# SHASwitch3.net
KiCad netlist of a schematic drawn in EAGLE
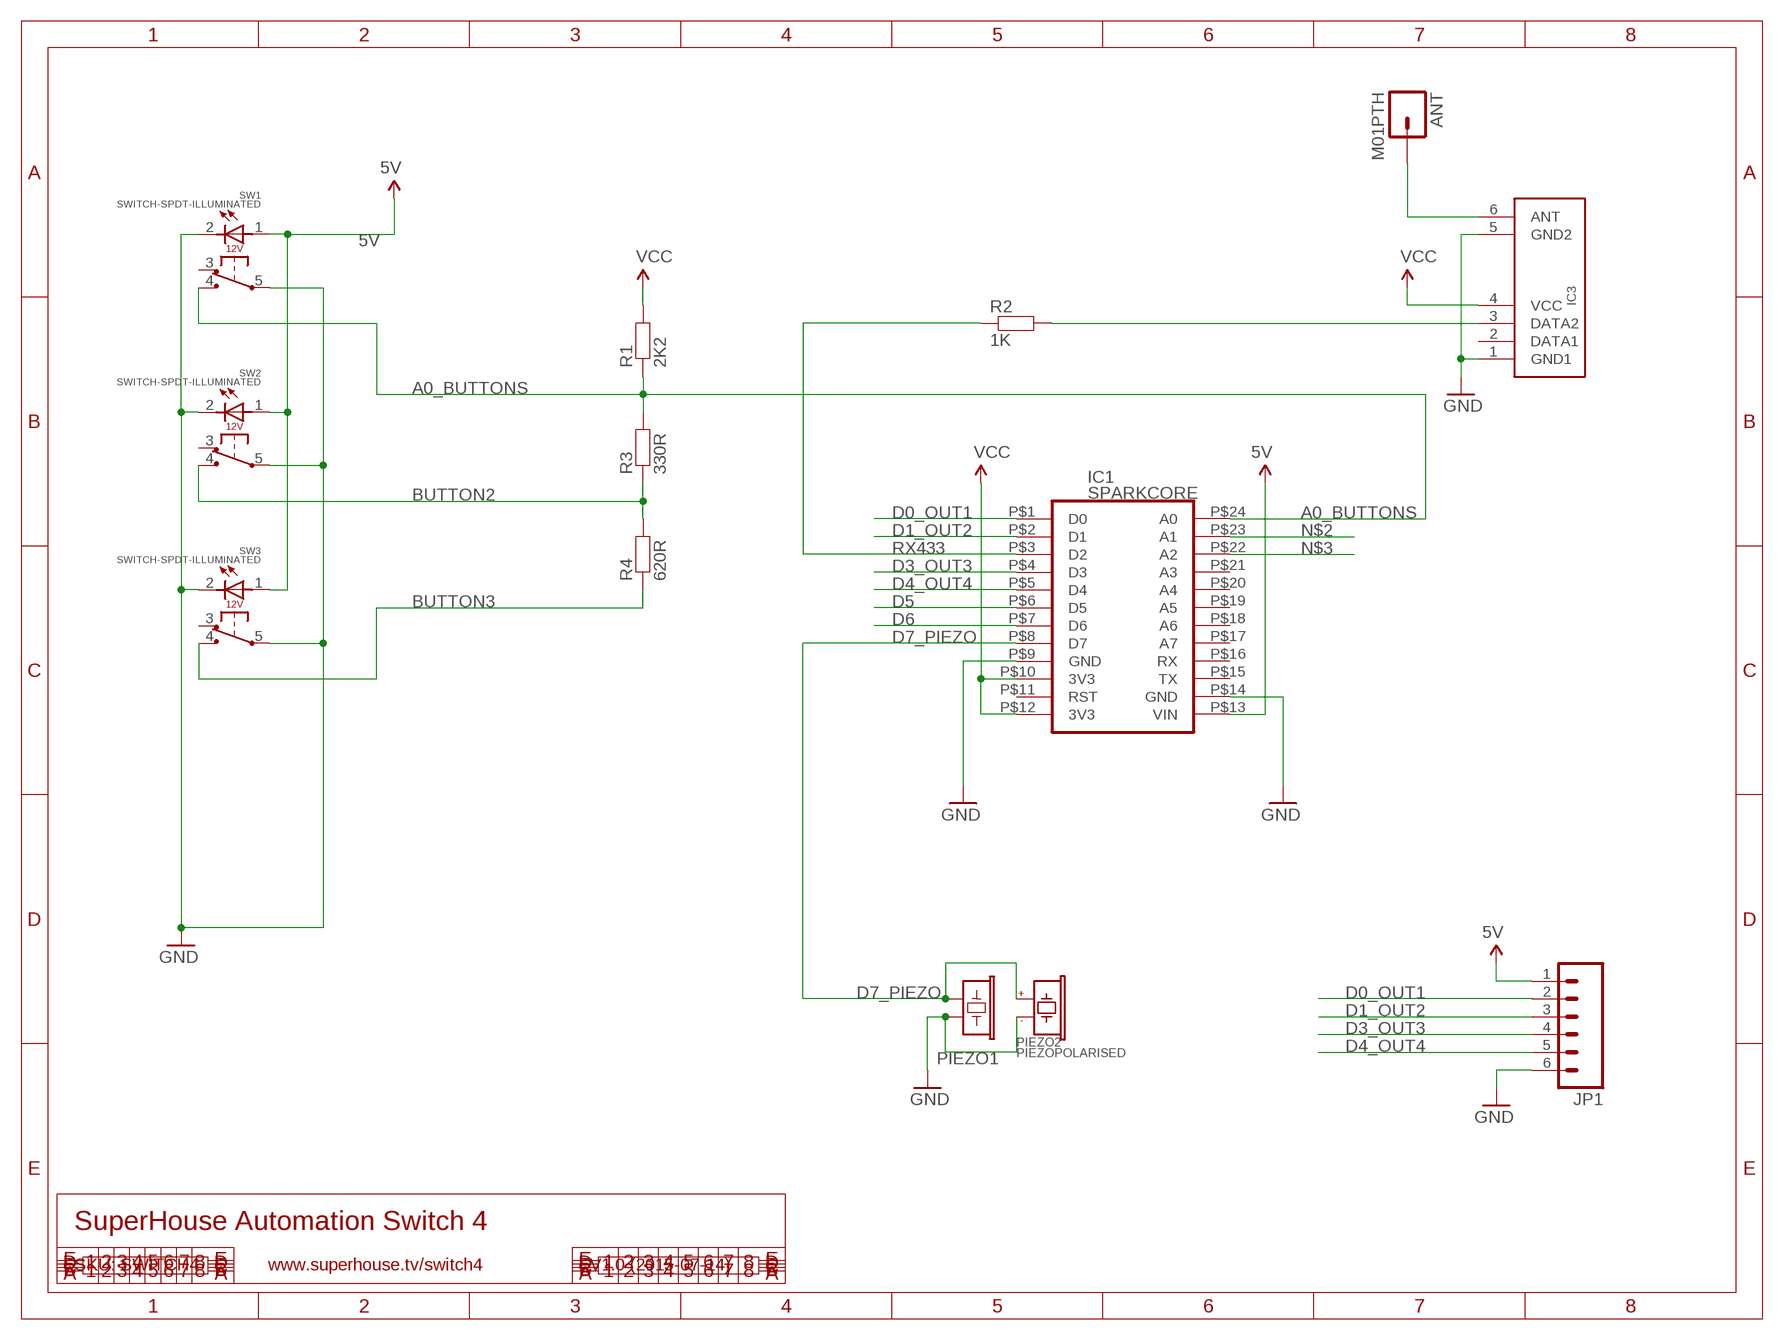
[diagram p0: schematic, sheet 1]

(export (version "E")
  (design (tool "Eeschema 10.0.6"))
  (components
    (comp (ref "ANT")
      (value "M01PTH")
      (footprint "eagle-import:1X01")
      (libsource (lib "eagle-import") (part "M01PTH"))
    )
    (comp (ref "IC1")
      (value "SPARKCORE")
      (footprint "eagle-import:SPARKCORE")
      (libsource (lib "eagle-import") (part "SPARKCORE"))
    )
    (comp (ref "IC3")
      (value "RXB1")
      (footprint "eagle-import:RX-B1-SHORT-FLAT")
      (libsource (lib "eagle-import") (part "RXB1SHORTFLAT"))
    )
    (comp (ref "JP1")
      (value "M06SIP")
      (footprint "eagle-import:1X06")
      (libsource (lib "eagle-import") (part "M06SIP"))
    )
    (comp (ref "PIEZO1")
      (value "BUZZERSMD12X12")
      (footprint "eagle-import:BUZZER-12X12-SMT")
      (libsource (lib "eagle-import") (part "BUZZERSMD12X12"))
    )
    (comp (ref "PIEZO2")
      (value "PIEZOPOLARISED")
      (footprint "eagle-import:PIEZO12MMWIDEPOLARISED")
      (libsource (lib "eagle-import") (part "PIEZOPOLARISED"))
    )
    (comp (ref "R1")
      (value "2K2")
      (footprint "eagle-import:0603")
      (libsource (lib "eagle-import") (part "RESISTOR0603"))
    )
    (comp (ref "R2")
      (value "1K")
      (footprint "eagle-import:0603")
      (libsource (lib "eagle-import") (part "RESISTOR0603"))
    )
    (comp (ref "R3")
      (value "330R")
      (footprint "eagle-import:0603")
      (libsource (lib "eagle-import") (part "RESISTOR0603"))
    )
    (comp (ref "R4")
      (value "620R")
      (footprint "eagle-import:0603")
      (libsource (lib "eagle-import") (part "RESISTOR0603"))
    )
    (comp (ref "SW1")
      (value "SWITCH-SPDT-ILLUMINATED")
      (footprint "eagle-import:SWITCH-SPDT-ILLUMINATED")
      (libsource (lib "eagle-import") (part "SWITCH-SPDT-ILLUMINATED"))
    )
    (comp (ref "SW2")
      (value "SWITCH-SPDT-ILLUMINATED")
      (footprint "eagle-import:SWITCH-SPDT-ILLUMINATED")
      (libsource (lib "eagle-import") (part "SWITCH-SPDT-ILLUMINATED"))
    )
    (comp (ref "SW3")
      (value "SWITCH-SPDT-ILLUMINATED")
      (footprint "eagle-import:SWITCH-SPDT-ILLUMINATED")
      (libsource (lib "eagle-import") (part "SWITCH-SPDT-ILLUMINATED"))
    )
  )
  (nets
    (net (code "1") (name "/A0_BUTTONS") (class "Default")
      (node (ref "IC1") (pin "P$24") (pinfunction "A0_P$24") (pintype "bidirectional"))
      (node (ref "R1") (pin "1") (pinfunction "1_1") (pintype "passive"))
      (node (ref "R3") (pin "2") (pinfunction "2_2") (pintype "passive"))
      (node (ref "SW1") (pin "4") (pinfunction "NO_4") (pintype "passive"))
    )
    (net (code "2") (name "/BUTTON2") (class "Default")
      (node (ref "R3") (pin "1") (pinfunction "1_1") (pintype "passive"))
      (node (ref "R4") (pin "2") (pinfunction "2_2") (pintype "passive"))
      (node (ref "SW2") (pin "4") (pinfunction "NO_4") (pintype "passive"))
    )
    (net (code "3") (name "/BUTTON3") (class "Default")
      (node (ref "R4") (pin "1") (pinfunction "1_1") (pintype "passive"))
      (node (ref "SW3") (pin "4") (pinfunction "NO_4") (pintype "passive"))
    )
    (net (code "4") (name "/D0_OUT1") (class "Default")
      (node (ref "IC1") (pin "P$1") (pinfunction "D0_P$1") (pintype "bidirectional"))
      (node (ref "JP1") (pin "2") (pinfunction "2_2") (pintype "passive"))
    )
    (net (code "5") (name "/D1_OUT2") (class "Default")
      (node (ref "IC1") (pin "P$2") (pinfunction "D1_P$2") (pintype "bidirectional"))
      (node (ref "JP1") (pin "3") (pinfunction "3_3") (pintype "passive"))
    )
    (net (code "6") (name "/D3_OUT3") (class "Default")
      (node (ref "IC1") (pin "P$4") (pinfunction "D3_P$4") (pintype "bidirectional"))
      (node (ref "JP1") (pin "4") (pinfunction "4_4") (pintype "passive"))
    )
    (net (code "7") (name "/D4_OUT4") (class "Default")
      (node (ref "IC1") (pin "P$5") (pinfunction "D4_P$5") (pintype "bidirectional"))
      (node (ref "JP1") (pin "5") (pinfunction "5_5") (pintype "passive"))
    )
    (net (code "8") (name "/D5") (class "Default")
      (node (ref "IC1") (pin "P$6") (pinfunction "D5_P$6") (pintype "bidirectional"))
    )
    (net (code "9") (name "/D6") (class "Default")
      (node (ref "IC1") (pin "P$7") (pinfunction "D6_P$7") (pintype "bidirectional"))
    )
    (net (code "10") (name "/D7_PIEZO") (class "Default")
      (node (ref "IC1") (pin "P$8") (pinfunction "D7_P$8") (pintype "bidirectional"))
      (node (ref "PIEZO1") (pin "1") (pinfunction "1_1") (pintype "passive"))
      (node (ref "PIEZO2") (pin "1") (pinfunction "+_1") (pintype "bidirectional"))
    )
    (net (code "11") (name "/N$2") (class "Default")
      (node (ref "IC1") (pin "P$23") (pinfunction "A1_P$23") (pintype "bidirectional"))
    )
    (net (code "12") (name "/N$3") (class "Default")
      (node (ref "IC1") (pin "P$22") (pinfunction "A2_P$22") (pintype "bidirectional"))
    )
    (net (code "13") (name "/RX433") (class "Default")
      (node (ref "IC1") (pin "P$3") (pinfunction "D2_P$3") (pintype "bidirectional"))
      (node (ref "R2") (pin "1") (pinfunction "1_1") (pintype "passive"))
    )
    (net (code "14") (name "5V") (class "Default")
      (node (ref "IC1") (pin "P$13") (pinfunction "VIN_P$13") (pintype "bidirectional"))
      (node (ref "JP1") (pin "1") (pinfunction "1_1") (pintype "passive"))
      (node (ref "SW1") (pin "1") (pinfunction "+_1") (pintype "passive"))
      (node (ref "SW2") (pin "1") (pinfunction "+_1") (pintype "passive"))
      (node (ref "SW3") (pin "1") (pinfunction "+_1") (pintype "passive"))
    )
    (net (code "15") (name "GND") (class "Default")
      (node (ref "IC1") (pin "P$14") (pinfunction "GND_P$14") (pintype "bidirectional"))
      (node (ref "IC1") (pin "P$9") (pinfunction "GND_P$9") (pintype "bidirectional"))
      (node (ref "IC3") (pin "1") (pinfunction "GND1_1") (pintype "bidirectional"))
      (node (ref "IC3") (pin "5") (pinfunction "GND2_5") (pintype "bidirectional"))
      (node (ref "JP1") (pin "6") (pinfunction "6_6") (pintype "passive"))
      (node (ref "PIEZO1") (pin "2") (pinfunction "2_2") (pintype "passive"))
      (node (ref "PIEZO2") (pin "2") (pinfunction "-_2") (pintype "bidirectional"))
      (node (ref "SW1") (pin "2") (pinfunction "-_2") (pintype "passive"))
      (node (ref "SW1") (pin "5") (pinfunction "COM_5") (pintype "passive"))
      (node (ref "SW2") (pin "2") (pinfunction "-_2") (pintype "passive"))
      (node (ref "SW2") (pin "5") (pinfunction "COM_5") (pintype "passive"))
      (node (ref "SW3") (pin "2") (pinfunction "-_2") (pintype "passive"))
      (node (ref "SW3") (pin "5") (pinfunction "COM_5") (pintype "passive"))
    )
    (net (code "16") (name "Net-(IC3-ANT)") (class "Default")
      (node (ref "ANT") (pin "1") (pinfunction "1_1") (pintype "passive"))
      (node (ref "IC3") (pin "6") (pinfunction "ANT_6") (pintype "bidirectional"))
    )
    (net (code "17") (name "Net-(IC3-DATA2)") (class "Default")
      (node (ref "IC3") (pin "3") (pinfunction "DATA2_3") (pintype "bidirectional"))
      (node (ref "R2") (pin "2") (pinfunction "2_2") (pintype "passive"))
    )
    (net (code "18") (name "VCC") (class "Default")
      (node (ref "IC1") (pin "P$10") (pinfunction "3V3_P$10") (pintype "bidirectional"))
      (node (ref "IC1") (pin "P$12") (pinfunction "3V3_P$12") (pintype "bidirectional"))
      (node (ref "IC3") (pin "4") (pinfunction "VCC_4") (pintype "bidirectional"))
      (node (ref "R1") (pin "2") (pinfunction "2_2") (pintype "passive"))
    )
    (net (code "19") (name "unconnected-(IC1-A3-PadP$21)") (class "Default")
      (node (ref "IC1") (pin "P$21") (pinfunction "A3_P$21") (pintype "bidirectional"))
    )
    (net (code "20") (name "unconnected-(IC1-A4-PadP$20)") (class "Default")
      (node (ref "IC1") (pin "P$20") (pinfunction "A4_P$20") (pintype "bidirectional"))
    )
    (net (code "21") (name "unconnected-(IC1-A5-PadP$19)") (class "Default")
      (node (ref "IC1") (pin "P$19") (pinfunction "A5_P$19") (pintype "bidirectional"))
    )
    (net (code "22") (name "unconnected-(IC1-A6-PadP$18)") (class "Default")
      (node (ref "IC1") (pin "P$18") (pinfunction "A6_P$18") (pintype "bidirectional"))
    )
    (net (code "23") (name "unconnected-(IC1-A7-PadP$17)") (class "Default")
      (node (ref "IC1") (pin "P$17") (pinfunction "A7_P$17") (pintype "bidirectional"))
    )
    (net (code "24") (name "unconnected-(IC1-RST-PadP$11)") (class "Default")
      (node (ref "IC1") (pin "P$11") (pinfunction "RST_P$11") (pintype "bidirectional"))
    )
    (net (code "25") (name "unconnected-(IC1-RX-PadP$16)") (class "Default")
      (node (ref "IC1") (pin "P$16") (pinfunction "RX_P$16") (pintype "bidirectional"))
    )
    (net (code "26") (name "unconnected-(IC1-TX-PadP$15)") (class "Default")
      (node (ref "IC1") (pin "P$15") (pinfunction "TX_P$15") (pintype "bidirectional"))
    )
    (net (code "27") (name "unconnected-(IC3-DATA1-Pad2)") (class "Default")
      (node (ref "IC3") (pin "2") (pinfunction "DATA1_2") (pintype "bidirectional"))
    )
    (net (code "28") (name "unconnected-(SW1-NC-Pad3)") (class "Default")
      (node (ref "SW1") (pin "3") (pinfunction "NC_3") (pintype "passive"))
    )
    (net (code "29") (name "unconnected-(SW2-NC-Pad3)") (class "Default")
      (node (ref "SW2") (pin "3") (pinfunction "NC_3") (pintype "passive"))
    )
    (net (code "30") (name "unconnected-(SW3-NC-Pad3)") (class "Default")
      (node (ref "SW3") (pin "3") (pinfunction "NC_3") (pintype "passive"))
    )
  )
)
